# Tiny_Tetris_v1_1.net
KiCad netlist of a schematic drawn in EAGLE
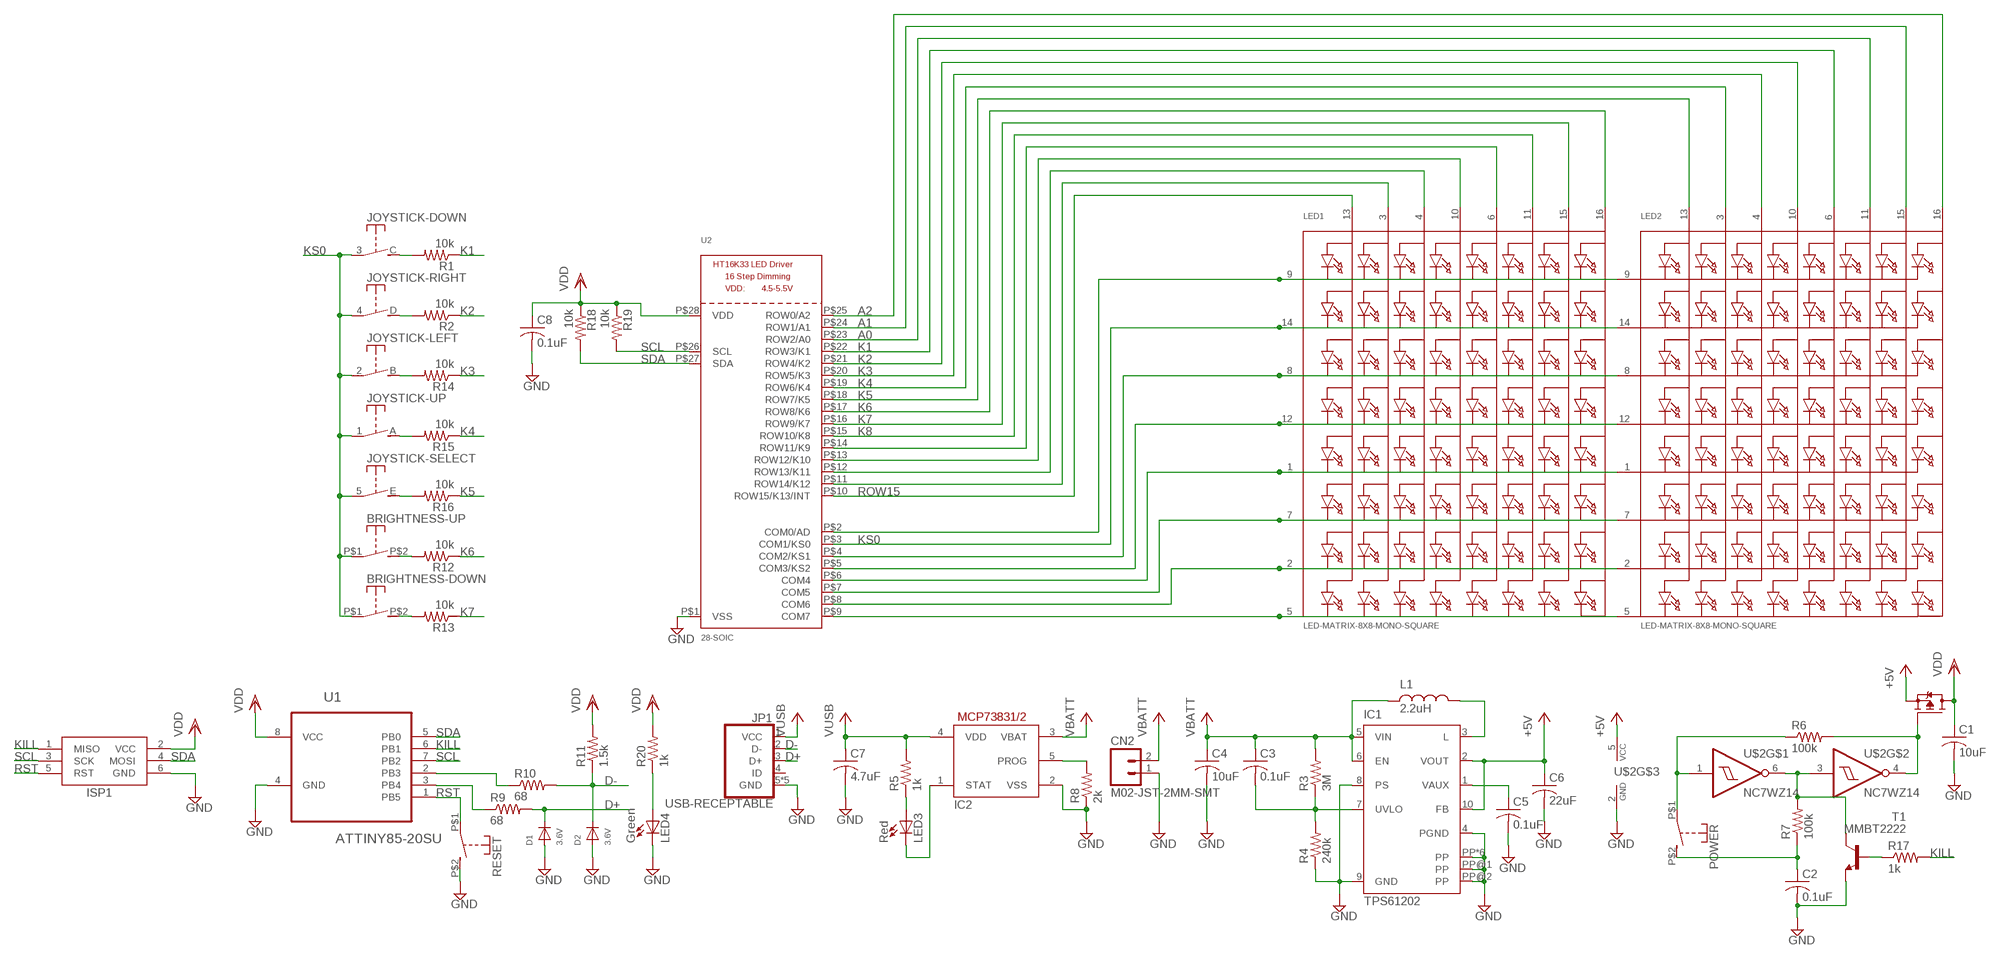
[diagram p0: schematic, sheet 1]

(export (version "E")
  (design (tool "Eeschema 10.0.6"))
  (components
    (comp (ref "BRIGHTNESS-DOWN")
      (value "SWITCH-TACTSKRELGE010")
      (footprint "eagle-import:TACT-ALPS-SKRELGE010")
      (libsource (lib "eagle-import") (part "SWITCH-TACTSKRELGE010"))
    )
    (comp (ref "BRIGHTNESS-UP")
      (value "SWITCH-TACTSKRELGE010")
      (footprint "eagle-import:TACT-ALPS-SKRELGE010")
      (libsource (lib "eagle-import") (part "SWITCH-TACTSKRELGE010"))
    )
    (comp (ref "C1")
      (value "10uF")
      (footprint "eagle-import:C0603K")
      (libsource (lib "eagle-import") (part "C-USC0603K"))
    )
    (comp (ref "C2")
      (value "0.1uF")
      (footprint "eagle-import:C0603K")
      (libsource (lib "eagle-import") (part "C-USC0603K"))
    )
    (comp (ref "C3")
      (value "0.1uF")
      (footprint "eagle-import:C0603K")
      (libsource (lib "eagle-import") (part "C-USC0603K"))
    )
    (comp (ref "C4")
      (value "10uF")
      (footprint "eagle-import:C0603K")
      (libsource (lib "eagle-import") (part "C-USC0603K"))
    )
    (comp (ref "C5")
      (value "0.1uF")
      (footprint "eagle-import:C0603K")
      (libsource (lib "eagle-import") (part "C-USC0603K"))
    )
    (comp (ref "C6")
      (value "22uF")
      (footprint "eagle-import:C0603K")
      (libsource (lib "eagle-import") (part "C-USC0603K"))
    )
    (comp (ref "C7")
      (value "4.7uF")
      (footprint "eagle-import:C0603K")
      (libsource (lib "eagle-import") (part "C-USC0603K"))
    )
    (comp (ref "C8")
      (value "0.1uF")
      (footprint "eagle-import:C0603K")
      (libsource (lib "eagle-import") (part "C-USC0603K"))
    )
    (comp (ref "CN2")
      (value "M02-JST-2MM-SMT")
      (footprint "eagle-import:1X02_NO_SILK")
      (libsource (lib "eagle-import") (part "M021X02_NO_SILK"))
    )
    (comp (ref "D1")
      (value "3.6V")
      (footprint "eagle-import:SOD-323")
      (libsource (lib "eagle-import") (part "DIODESOD-323"))
    )
    (comp (ref "D2")
      (value "3.6V")
      (footprint "eagle-import:SOD-323")
      (libsource (lib "eagle-import") (part "DIODESOD-323"))
    )
    (comp (ref "IC1")
      (value "TPS61202")
      (footprint "eagle-import:S-PDSO-N10")
      (fields (field (name "MPN") "TPS61202DRCR"))
      (libsource (lib "eagle-import") (part "TPS61202"))
    )
    (comp (ref "IC2")
      (value "MCP73831/OT")
      (footprint "eagle-import:SOT23-5L")
      (libsource (lib "eagle-import") (part "MCP73831/OT"))
    )
    (comp (ref "ISP1")
      (value "AVRISP-6")
      (footprint "eagle-import:AVRISP")
      (libsource (lib "eagle-import") (part "AVRISP-6"))
    )
    (comp (ref "JOYSTICK-")
      (value "SWITCH-NAVIGATION")
      (footprint "eagle-import:JOYSTICK-NOKIA-3230")
      (libsource (lib "eagle-import") (part "SWITCH-NAVIGATION"))
    )
    (comp (ref "JP1")
      (value "USB-RECEPTABLE")
      (footprint "eagle-import:FCI-10103594-0001LF")
      (libsource (lib "eagle-import") (part "USB-RECEPTABLE"))
    )
    (comp (ref "L1")
      (value "2.2uH")
      (footprint "eagle-import:LPS3015")
      (libsource (lib "eagle-import") (part "LPS3015"))
    )
    (comp (ref "LED1")
      (value "LED-MATRIX-8X8-MONO-SQUARE")
      (footprint "eagle-import:LED-MATRIX-8X8-MONO-SQUARE")
      (libsource (lib "eagle-import") (part "LED-MATRIX-8X8-MONO-SQUARE"))
    )
    (comp (ref "LED2")
      (value "LED-MATRIX-8X8-MONO-SQUARE")
      (footprint "eagle-import:LED-MATRIX-8X8-MONO-SQUARE")
      (libsource (lib "eagle-import") (part "LED-MATRIX-8X8-MONO-SQUARE"))
    )
    (comp (ref "LED3")
      (value "Red")
      (footprint "eagle-import:LED-0603-SIDEVIEW")
      (libsource (lib "eagle-import") (part "LED"))
    )
    (comp (ref "LED4")
      (value "Green")
      (footprint "eagle-import:LED-0603-SIDEVIEW")
      (libsource (lib "eagle-import") (part "LED"))
    )
    (comp (ref "POWER")
      (value "SWITCH-TACTSKRELGE010")
      (footprint "eagle-import:TACT-ALPS-SKRELGE010")
      (libsource (lib "eagle-import") (part "SWITCH-TACTSKRELGE010"))
    )
    (comp (ref "R1")
      (value "10k")
      (footprint "eagle-import:R0603")
      (libsource (lib "eagle-import") (part "R-US_R0603"))
    )
    (comp (ref "R2")
      (value "10k")
      (footprint "eagle-import:R0603")
      (libsource (lib "eagle-import") (part "R-US_R0603"))
    )
    (comp (ref "R3")
      (value "3M")
      (footprint "eagle-import:R0603")
      (libsource (lib "eagle-import") (part "R-US_R0603"))
    )
    (comp (ref "R4")
      (value "240k")
      (footprint "eagle-import:R0603")
      (libsource (lib "eagle-import") (part "R-US_R0603"))
    )
    (comp (ref "R5")
      (value "1k")
      (footprint "eagle-import:R0603")
      (libsource (lib "eagle-import") (part "R-US_R0603"))
    )
    (comp (ref "R6")
      (value "100k")
      (footprint "eagle-import:R0603")
      (libsource (lib "eagle-import") (part "R-US_R0603"))
    )
    (comp (ref "R7")
      (value "100k")
      (footprint "eagle-import:R0603")
      (libsource (lib "eagle-import") (part "R-US_R0603"))
    )
    (comp (ref "R8")
      (value "2k")
      (footprint "eagle-import:R0603")
      (libsource (lib "eagle-import") (part "R-US_R0603"))
    )
    (comp (ref "R9")
      (value "68")
      (footprint "eagle-import:R0603")
      (libsource (lib "eagle-import") (part "R-US_R0603"))
    )
    (comp (ref "R10")
      (value "68")
      (footprint "eagle-import:R0603")
      (libsource (lib "eagle-import") (part "R-US_R0603"))
    )
    (comp (ref "R11")
      (value "1.5k")
      (footprint "eagle-import:R0603")
      (libsource (lib "eagle-import") (part "R-US_R0603"))
    )
    (comp (ref "R12")
      (value "10k")
      (footprint "eagle-import:R0603")
      (libsource (lib "eagle-import") (part "R-US_R0603"))
    )
    (comp (ref "R13")
      (value "10k")
      (footprint "eagle-import:R0603")
      (libsource (lib "eagle-import") (part "R-US_R0603"))
    )
    (comp (ref "R14")
      (value "10k")
      (footprint "eagle-import:R0603")
      (libsource (lib "eagle-import") (part "R-US_R0603"))
    )
    (comp (ref "R15")
      (value "10k")
      (footprint "eagle-import:R0603")
      (libsource (lib "eagle-import") (part "R-US_R0603"))
    )
    (comp (ref "R16")
      (value "10k")
      (footprint "eagle-import:R0603")
      (libsource (lib "eagle-import") (part "R-US_R0603"))
    )
    (comp (ref "R17")
      (value "1k")
      (footprint "eagle-import:R0603")
      (libsource (lib "eagle-import") (part "R-US_R0603"))
    )
    (comp (ref "R18")
      (value "10k")
      (footprint "eagle-import:R0603")
      (libsource (lib "eagle-import") (part "R-US_R0603"))
    )
    (comp (ref "R19")
      (value "10k")
      (footprint "eagle-import:R0603")
      (libsource (lib "eagle-import") (part "R-US_R0603"))
    )
    (comp (ref "R20")
      (value "1k")
      (footprint "eagle-import:R0603")
      (libsource (lib "eagle-import") (part "R-US_R0603"))
    )
    (comp (ref "RESET")
      (value "SWITCH-TACTSKRELGE010")
      (footprint "eagle-import:TACT-ALPS-SKRELGE010")
      (libsource (lib "eagle-import") (part "SWITCH-TACTSKRELGE010"))
    )
    (comp (ref "T1")
      (value "MMBT2222")
      (footprint "eagle-import:SOT23-BEC")
      (libsource (lib "eagle-import") (part "-NPN-SOT23-BECMMBT2222ALT1"))
    )
    (comp (ref "U$1")
      (value "IRLML6402")
      (footprint "eagle-import:SOT23")
      (libsource (lib "eagle-import") (part "IRLML6402"))
    )
    (comp (ref "U$2")
      (value "NC7WZ14")
      (footprint "eagle-import:SC-70-6")
      (libsource (lib "eagle-import") (part "NC7WZ14"))
    )
    (comp (ref "U1")
      (value "ATTINY85-20SU")
      (footprint "eagle-import:SOIC127P798X216-8N")
      (libsource (lib "eagle-import") (part "ATTINY85-20SU"))
    )
    (comp (ref "U2")
      (value "28-SOIC")
      (footprint "eagle-import:SOP28_300MIL")
      (libsource (lib "eagle-import") (part "HT16K33_SOP28"))
    )
  )
  (nets
    (net (code "1") (name "+5V") (class "Default")
      (node (ref "C6") (pin "1") (pinfunction "1_1") (pintype "passive"))
      (node (ref "IC1") (pin "10") (pinfunction "FB_10") (pintype "input"))
      (node (ref "IC1") (pin "2") (pinfunction "VOUT_2") (pintype "passive"))
      (node (ref "U$1") (pin "2") (pinfunction "S_2") (pintype "passive"))
      (node (ref "U$2") (pin "5") (pinfunction "VCC_5") (pintype "power_in"))
    )
    (net (code "2") (name "/A0") (class "Default")
      (node (ref "LED2") (pin "11") (pinfunction "A6_11") (pintype "bidirectional"))
      (node (ref "U2") (pin "P$23") (pinfunction "ROW2/A0_P$23") (pintype "bidirectional"))
    )
    (net (code "3") (name "/A1") (class "Default")
      (node (ref "LED2") (pin "15") (pinfunction "A7_15") (pintype "bidirectional"))
      (node (ref "U2") (pin "P$24") (pinfunction "ROW1/A1_P$24") (pintype "bidirectional"))
    )
    (net (code "4") (name "/A2") (class "Default")
      (node (ref "LED2") (pin "16") (pinfunction "A8_16") (pintype "bidirectional"))
      (node (ref "U2") (pin "P$25") (pinfunction "ROW0/A2_P$25") (pintype "bidirectional"))
    )
    (net (code "5") (name "/D+") (class "Default")
      (node (ref "D1") (pin "C") (pinfunction "C_C") (pintype "passive"))
      (node (ref "JP1") (pin "3") (pinfunction "D+_3") (pintype "bidirectional"))
      (node (ref "R9") (pin "2") (pinfunction "2_2") (pintype "passive"))
    )
    (net (code "6") (name "/D-") (class "Default")
      (node (ref "D2") (pin "C") (pinfunction "C_C") (pintype "passive"))
      (node (ref "JP1") (pin "2") (pinfunction "D-_2") (pintype "bidirectional"))
      (node (ref "R10") (pin "2") (pinfunction "2_2") (pintype "passive"))
      (node (ref "R11") (pin "1") (pinfunction "1_1") (pintype "passive"))
    )
    (net (code "7") (name "/K1") (class "Default")
      (node (ref "LED2") (pin "6") (pinfunction "A5_6") (pintype "bidirectional"))
      (node (ref "R1") (pin "1") (pinfunction "1_1") (pintype "passive"))
      (node (ref "U2") (pin "P$22") (pinfunction "ROW3/K1_P$22") (pintype "bidirectional"))
    )
    (net (code "8") (name "/K2") (class "Default")
      (node (ref "LED2") (pin "10") (pinfunction "A4_10") (pintype "bidirectional"))
      (node (ref "R2") (pin "1") (pinfunction "1_1") (pintype "passive"))
      (node (ref "U2") (pin "P$21") (pinfunction "ROW4/K2_P$21") (pintype "bidirectional"))
    )
    (net (code "9") (name "/K3") (class "Default")
      (node (ref "LED2") (pin "4") (pinfunction "A3_4") (pintype "bidirectional"))
      (node (ref "R14") (pin "1") (pinfunction "1_1") (pintype "passive"))
      (node (ref "U2") (pin "P$20") (pinfunction "ROW5/K3_P$20") (pintype "bidirectional"))
    )
    (net (code "10") (name "/K4") (class "Default")
      (node (ref "LED2") (pin "3") (pinfunction "A2_3") (pintype "bidirectional"))
      (node (ref "R15") (pin "1") (pinfunction "1_1") (pintype "passive"))
      (node (ref "U2") (pin "P$19") (pinfunction "ROW6/K4_P$19") (pintype "bidirectional"))
    )
    (net (code "11") (name "/K5") (class "Default")
      (node (ref "LED2") (pin "13") (pinfunction "A1_13") (pintype "bidirectional"))
      (node (ref "R16") (pin "1") (pinfunction "1_1") (pintype "passive"))
      (node (ref "U2") (pin "P$18") (pinfunction "ROW7/K5_P$18") (pintype "bidirectional"))
    )
    (net (code "12") (name "/K6") (class "Default")
      (node (ref "LED1") (pin "16") (pinfunction "A8_16") (pintype "bidirectional"))
      (node (ref "R12") (pin "1") (pinfunction "1_1") (pintype "passive"))
      (node (ref "U2") (pin "P$17") (pinfunction "ROW8/K6_P$17") (pintype "bidirectional"))
    )
    (net (code "13") (name "/K7") (class "Default")
      (node (ref "LED1") (pin "15") (pinfunction "A7_15") (pintype "bidirectional"))
      (node (ref "R13") (pin "1") (pinfunction "1_1") (pintype "passive"))
      (node (ref "U2") (pin "P$16") (pinfunction "ROW9/K7_P$16") (pintype "bidirectional"))
    )
    (net (code "14") (name "/K8") (class "Default")
      (node (ref "LED1") (pin "11") (pinfunction "A6_11") (pintype "bidirectional"))
      (node (ref "U2") (pin "P$15") (pinfunction "ROW10/K8_P$15") (pintype "bidirectional"))
    )
    (net (code "15") (name "/KILL") (class "Default")
      (node (ref "ISP1") (pin "1") (pinfunction "MISO_1") (pintype "input"))
      (node (ref "R17") (pin "2") (pinfunction "2_2") (pintype "passive"))
      (node (ref "U1") (pin "6") (pinfunction "PB1_6") (pintype "bidirectional"))
    )
    (net (code "16") (name "/KS0") (class "Default")
      (node (ref "BRIGHTNESS-DOWN") (pin "P$1") (pinfunction "P_P$1") (pintype "passive"))
      (node (ref "BRIGHTNESS-UP") (pin "P$1") (pinfunction "P_P$1") (pintype "passive"))
      (node (ref "JOYSTICK-") (pin "1") (pinfunction "P_1") (pintype "passive"))
      (node (ref "JOYSTICK-") (pin "2") (pinfunction "P_2") (pintype "passive"))
      (node (ref "JOYSTICK-") (pin "3") (pinfunction "P_3") (pintype "passive"))
      (node (ref "JOYSTICK-") (pin "4") (pinfunction "P_4") (pintype "passive"))
      (node (ref "JOYSTICK-") (pin "5") (pinfunction "P_5") (pintype "passive"))
      (node (ref "LED1") (pin "14") (pinfunction "K2_14") (pintype "bidirectional"))
      (node (ref "LED2") (pin "14") (pinfunction "K2_14") (pintype "bidirectional"))
      (node (ref "U2") (pin "P$3") (pinfunction "COM1/KS0_P$3") (pintype "bidirectional"))
    )
    (net (code "17") (name "/ROW15") (class "Default")
      (node (ref "LED1") (pin "13") (pinfunction "A1_13") (pintype "bidirectional"))
      (node (ref "U2") (pin "P$10") (pinfunction "ROW15/K13/INT_P$10") (pintype "bidirectional"))
    )
    (net (code "18") (name "/RST") (class "Default")
      (node (ref "ISP1") (pin "5") (pinfunction "RST_5") (pintype "output"))
      (node (ref "RESET") (pin "P$1") (pinfunction "P_P$1") (pintype "passive"))
      (node (ref "U1") (pin "1") (pinfunction "PB5_1") (pintype "bidirectional"))
    )
    (net (code "19") (name "/SCL") (class "Default")
      (node (ref "ISP1") (pin "3") (pinfunction "SCK_3") (pintype "output"))
      (node (ref "R19") (pin "2") (pinfunction "2_2") (pintype "passive"))
      (node (ref "U1") (pin "7") (pinfunction "PB2_7") (pintype "bidirectional"))
      (node (ref "U2") (pin "P$26") (pinfunction "SCL_P$26") (pintype "bidirectional"))
    )
    (net (code "20") (name "/SDA") (class "Default")
      (node (ref "ISP1") (pin "4") (pinfunction "MOSI_4") (pintype "output"))
      (node (ref "R18") (pin "2") (pinfunction "2_2") (pintype "passive"))
      (node (ref "U1") (pin "5") (pinfunction "PB0_5") (pintype "bidirectional"))
      (node (ref "U2") (pin "P$27") (pinfunction "SDA_P$27") (pintype "bidirectional"))
    )
    (net (code "21") (name "GND") (class "Default")
      (node (ref "C1") (pin "2") (pinfunction "2_2") (pintype "passive"))
      (node (ref "C2") (pin "2") (pinfunction "2_2") (pintype "passive"))
      (node (ref "C4") (pin "2") (pinfunction "2_2") (pintype "passive"))
      (node (ref "C5") (pin "2") (pinfunction "2_2") (pintype "passive"))
      (node (ref "C6") (pin "2") (pinfunction "2_2") (pintype "passive"))
      (node (ref "C7") (pin "2") (pinfunction "2_2") (pintype "passive"))
      (node (ref "C8") (pin "2") (pinfunction "2_2") (pintype "passive"))
      (node (ref "CN2") (pin "1") (pinfunction "1_1") (pintype "passive"))
      (node (ref "D1") (pin "A") (pinfunction "A_A") (pintype "passive"))
      (node (ref "D2") (pin "A") (pinfunction "A_A") (pintype "passive"))
      (node (ref "IC1") (pin "4") (pinfunction "PGND_4") (pintype "power_in"))
      (node (ref "IC1") (pin "8") (pinfunction "PS_8") (pintype "input"))
      (node (ref "IC1") (pin "9") (pinfunction "GND_9") (pintype "power_in"))
      (node (ref "IC1") (pin "PP") (pinfunction "PP_PP") (pintype "power_in"))
      (node (ref "IC1") (pin "PP@1") (pinfunction "PP_PP@1") (pintype "power_in"))
      (node (ref "IC1") (pin "PP@2") (pinfunction "PP_PP@2") (pintype "power_in"))
      (node (ref "IC1") (pin "PP@3") (pinfunction "PP_PP@3") (pintype "power_in"))
      (node (ref "IC1") (pin "PP@4") (pinfunction "PP_PP@4") (pintype "power_in"))
      (node (ref "IC1") (pin "PP@5") (pinfunction "PP_PP@5") (pintype "power_in"))
      (node (ref "IC1") (pin "PP@6") (pinfunction "PP_PP@6") (pintype "power_in"))
      (node (ref "IC1") (pin "PP@7") (pinfunction "PP_PP@7") (pintype "power_in"))
      (node (ref "IC2") (pin "2") (pinfunction "VSS_2") (pintype "power_in"))
      (node (ref "ISP1") (pin "6") (pinfunction "GND_6") (pintype "power_in"))
      (node (ref "JP1") (pin "5") (pinfunction "GND_5") (pintype "bidirectional"))
      (node (ref "JP1") (pin "P$1") (pinfunction "GND_P$1") (pintype "bidirectional"))
      (node (ref "JP1") (pin "P$2") (pinfunction "GND_P$2") (pintype "bidirectional"))
      (node (ref "JP1") (pin "P$3") (pinfunction "GND_P$3") (pintype "bidirectional"))
      (node (ref "JP1") (pin "P$4") (pinfunction "GND_P$4") (pintype "bidirectional"))
      (node (ref "LED4") (pin "P$2") (pinfunction "C_P$2") (pintype "passive"))
      (node (ref "R4") (pin "1") (pinfunction "1_1") (pintype "passive"))
      (node (ref "R8") (pin "1") (pinfunction "1_1") (pintype "passive"))
      (node (ref "RESET") (pin "P$2") (pinfunction "S_P$2") (pintype "passive"))
      (node (ref "T1") (pin "E") (pinfunction "E_E") (pintype "passive"))
      (node (ref "U$2") (pin "2") (pinfunction "GND_2") (pintype "power_in"))
      (node (ref "U1") (pin "4") (pinfunction "GND_4") (pintype "passive"))
      (node (ref "U2") (pin "P$1") (pinfunction "VSS_P$1") (pintype "bidirectional"))
    )
    (net (code "22") (name "Net-(BRIGHTNESS-DOWN-S)") (class "Default")
      (node (ref "BRIGHTNESS-DOWN") (pin "P$2") (pinfunction "S_P$2") (pintype "passive"))
      (node (ref "R13") (pin "2") (pinfunction "2_2") (pintype "passive"))
    )
    (net (code "23") (name "Net-(BRIGHTNESS-UP-S)") (class "Default")
      (node (ref "BRIGHTNESS-UP") (pin "P$2") (pinfunction "S_P$2") (pintype "passive"))
      (node (ref "R12") (pin "2") (pinfunction "2_2") (pintype "passive"))
    )
    (net (code "24") (name "Net-(IC1-L)") (class "Default")
      (node (ref "IC1") (pin "3") (pinfunction "L_3") (pintype "input"))
      (node (ref "L1") (pin "P$2") (pinfunction "P$2_P$2") (pintype "bidirectional"))
    )
    (net (code "25") (name "Net-(IC1-UVLO)") (class "Default")
      (node (ref "C3") (pin "2") (pinfunction "2_2") (pintype "passive"))
      (node (ref "IC1") (pin "7") (pinfunction "UVLO_7") (pintype "input"))
      (node (ref "R3") (pin "1") (pinfunction "1_1") (pintype "passive"))
      (node (ref "R4") (pin "2") (pinfunction "2_2") (pintype "passive"))
    )
    (net (code "26") (name "Net-(IC1-VAUX)") (class "Default")
      (node (ref "C5") (pin "1") (pinfunction "1_1") (pintype "passive"))
      (node (ref "IC1") (pin "1") (pinfunction "VAUX_1") (pintype "bidirectional"))
    )
    (net (code "27") (name "Net-(IC2-PROG)") (class "Default")
      (node (ref "IC2") (pin "5") (pinfunction "PROG_5") (pintype "input"))
      (node (ref "R8") (pin "2") (pinfunction "2_2") (pintype "passive"))
    )
    (net (code "28") (name "Net-(IC2-STAT)") (class "Default")
      (node (ref "IC2") (pin "1") (pinfunction "STAT_1") (pintype "output"))
      (node (ref "LED3") (pin "P$2") (pinfunction "C_P$2") (pintype "passive"))
    )
    (net (code "29") (name "Net-(JOYSTICK-A-S)") (class "Default")
      (node (ref "JOYSTICK-") (pin "C") (pinfunction "S_C") (pintype "passive"))
      (node (ref "R1") (pin "2") (pinfunction "2_2") (pintype "passive"))
    )
    (net (code "30") (name "Net-(JOYSTICK-B-S)") (class "Default")
      (node (ref "JOYSTICK-") (pin "B") (pinfunction "S_B") (pintype "passive"))
      (node (ref "R14") (pin "2") (pinfunction "2_2") (pintype "passive"))
    )
    (net (code "31") (name "Net-(JOYSTICK-C-S)") (class "Default")
      (node (ref "JOYSTICK-") (pin "D") (pinfunction "S_D") (pintype "passive"))
      (node (ref "R2") (pin "2") (pinfunction "2_2") (pintype "passive"))
    )
    (net (code "32") (name "Net-(JOYSTICK-D-S)") (class "Default")
      (node (ref "JOYSTICK-") (pin "E") (pinfunction "S_E") (pintype "passive"))
      (node (ref "R16") (pin "2") (pinfunction "2_2") (pintype "passive"))
    )
    (net (code "33") (name "Net-(JOYSTICK-E-S)") (class "Default")
      (node (ref "JOYSTICK-") (pin "A") (pinfunction "S_A") (pintype "passive"))
      (node (ref "R15") (pin "2") (pinfunction "2_2") (pintype "passive"))
    )
    (net (code "34") (name "Net-(LED1-A2)") (class "Default")
      (node (ref "LED1") (pin "3") (pinfunction "A2_3") (pintype "bidirectional"))
      (node (ref "U2") (pin "P$11") (pinfunction "ROW14/K12_P$11") (pintype "bidirectional"))
    )
    (net (code "35") (name "Net-(LED1-A3)") (class "Default")
      (node (ref "LED1") (pin "4") (pinfunction "A3_4") (pintype "bidirectional"))
      (node (ref "U2") (pin "P$12") (pinfunction "ROW13/K11_P$12") (pintype "bidirectional"))
    )
    (net (code "36") (name "Net-(LED1-A4)") (class "Default")
      (node (ref "LED1") (pin "10") (pinfunction "A4_10") (pintype "bidirectional"))
      (node (ref "U2") (pin "P$13") (pinfunction "ROW12/K10_P$13") (pintype "bidirectional"))
    )
    (net (code "37") (name "Net-(LED1-A5)") (class "Default")
      (node (ref "LED1") (pin "6") (pinfunction "A5_6") (pintype "bidirectional"))
      (node (ref "U2") (pin "P$14") (pinfunction "ROW11/K9_P$14") (pintype "bidirectional"))
    )
    (net (code "38") (name "Net-(LED1-K1)") (class "Default")
      (node (ref "LED1") (pin "9") (pinfunction "K1_9") (pintype "bidirectional"))
      (node (ref "LED2") (pin "9") (pinfunction "K1_9") (pintype "bidirectional"))
      (node (ref "U2") (pin "P$2") (pinfunction "COM0/AD_P$2") (pintype "bidirectional"))
    )
    (net (code "39") (name "Net-(LED1-K3)") (class "Default")
      (node (ref "LED1") (pin "8") (pinfunction "K3_8") (pintype "bidirectional"))
      (node (ref "LED2") (pin "8") (pinfunction "K3_8") (pintype "bidirectional"))
      (node (ref "U2") (pin "P$4") (pinfunction "COM2/KS1_P$4") (pintype "bidirectional"))
    )
    (net (code "40") (name "Net-(LED1-K4)") (class "Default")
      (node (ref "LED1") (pin "12") (pinfunction "K4_12") (pintype "bidirectional"))
      (node (ref "LED2") (pin "12") (pinfunction "K4_12") (pintype "bidirectional"))
      (node (ref "U2") (pin "P$5") (pinfunction "COM3/KS2_P$5") (pintype "bidirectional"))
    )
    (net (code "41") (name "Net-(LED1-K5)") (class "Default")
      (node (ref "LED1") (pin "1") (pinfunction "K5_1") (pintype "bidirectional"))
      (node (ref "LED2") (pin "1") (pinfunction "K5_1") (pintype "bidirectional"))
      (node (ref "U2") (pin "P$6") (pinfunction "COM4_P$6") (pintype "bidirectional"))
    )
    (net (code "42") (name "Net-(LED1-K6)") (class "Default")
      (node (ref "LED1") (pin "7") (pinfunction "K6_7") (pintype "bidirectional"))
      (node (ref "LED2") (pin "7") (pinfunction "K6_7") (pintype "bidirectional"))
      (node (ref "U2") (pin "P$7") (pinfunction "COM5_P$7") (pintype "bidirectional"))
    )
    (net (code "43") (name "Net-(LED1-K7)") (class "Default")
      (node (ref "LED1") (pin "2") (pinfunction "K7_2") (pintype "bidirectional"))
      (node (ref "LED2") (pin "2") (pinfunction "K7_2") (pintype "bidirectional"))
      (node (ref "U2") (pin "P$8") (pinfunction "COM6_P$8") (pintype "bidirectional"))
    )
    (net (code "44") (name "Net-(LED1-K8)") (class "Default")
      (node (ref "LED1") (pin "5") (pinfunction "K8_5") (pintype "bidirectional"))
      (node (ref "LED2") (pin "5") (pinfunction "K8_5") (pintype "bidirectional"))
      (node (ref "U2") (pin "P$9") (pinfunction "COM7_P$9") (pintype "bidirectional"))
    )
    (net (code "45") (name "Net-(LED3-A)") (class "Default")
      (node (ref "LED3") (pin "P$1") (pinfunction "A_P$1") (pintype "passive"))
      (node (ref "R5") (pin "1") (pinfunction "1_1") (pintype "passive"))
    )
    (net (code "46") (name "Net-(LED4-A)") (class "Default")
      (node (ref "LED4") (pin "P$1") (pinfunction "A_P$1") (pintype "passive"))
      (node (ref "R20") (pin "1") (pinfunction "1_1") (pintype "passive"))
    )
    (net (code "47") (name "Net-(POWER-P)") (class "Default")
      (node (ref "POWER") (pin "P$1") (pinfunction "P_P$1") (pintype "passive"))
      (node (ref "R6") (pin "1") (pinfunction "1_1") (pintype "passive"))
      (node (ref "U$2") (pin "1") (pinfunction "I_1") (pintype "input"))
    )
    (net (code "48") (name "Net-(POWER-S)") (class "Default")
      (node (ref "C2") (pin "1") (pinfunction "1_1") (pintype "passive"))
      (node (ref "POWER") (pin "P$2") (pinfunction "S_P$2") (pintype "passive"))
      (node (ref "R7") (pin "1") (pinfunction "1_1") (pintype "passive"))
    )
    (net (code "49") (name "Net-(R17-Pad1)") (class "Default")
      (node (ref "R17") (pin "1") (pinfunction "1_1") (pintype "passive"))
      (node (ref "T1") (pin "B") (pinfunction "B_B") (pintype "passive"))
    )
    (net (code "50") (name "Net-(U$1-G)") (class "Default")
      (node (ref "R6") (pin "2") (pinfunction "2_2") (pintype "passive"))
      (node (ref "U$1") (pin "1") (pinfunction "G_1") (pintype "passive"))
      (node (ref "U$2") (pin "4") (pinfunction "O_4") (pintype "output"))
    )
    (net (code "51") (name "Net-(U$2A-O)") (class "Default")
      (node (ref "R7") (pin "2") (pinfunction "2_2") (pintype "passive"))
      (node (ref "T1") (pin "C") (pinfunction "C_C") (pintype "passive"))
      (node (ref "U$2") (pin "3") (pinfunction "I_3") (pintype "input"))
      (node (ref "U$2") (pin "6") (pinfunction "O_6") (pintype "output"))
    )
    (net (code "52") (name "Net-(U1-PB3)") (class "Default")
      (node (ref "R10") (pin "1") (pinfunction "1_1") (pintype "passive"))
      (node (ref "U1") (pin "2") (pinfunction "PB3_2") (pintype "bidirectional"))
    )
    (net (code "53") (name "Net-(U1-PB4)") (class "Default")
      (node (ref "R9") (pin "1") (pinfunction "1_1") (pintype "passive"))
      (node (ref "U1") (pin "3") (pinfunction "PB4_3") (pintype "bidirectional"))
    )
    (net (code "54") (name "VBATT") (class "Default")
      (node (ref "C3") (pin "1") (pinfunction "1_1") (pintype "passive"))
      (node (ref "C4") (pin "1") (pinfunction "1_1") (pintype "passive"))
      (node (ref "CN2") (pin "2") (pinfunction "2_2") (pintype "passive"))
      (node (ref "IC1") (pin "5") (pinfunction "VIN_5") (pintype "input"))
      (node (ref "IC1") (pin "6") (pinfunction "EN_6") (pintype "input"))
      (node (ref "IC2") (pin "3") (pinfunction "VBAT_3") (pintype "bidirectional"))
      (node (ref "L1") (pin "P$1") (pinfunction "P$1_P$1") (pintype "bidirectional"))
      (node (ref "R3") (pin "2") (pinfunction "2_2") (pintype "passive"))
    )
    (net (code "55") (name "VDD") (class "Default")
      (node (ref "C1") (pin "1") (pinfunction "1_1") (pintype "passive"))
      (node (ref "C8") (pin "1") (pinfunction "1_1") (pintype "passive"))
      (node (ref "ISP1") (pin "2") (pinfunction "VCC_2") (pintype "power_in"))
      (node (ref "R11") (pin "2") (pinfunction "2_2") (pintype "passive"))
      (node (ref "R18") (pin "1") (pinfunction "1_1") (pintype "passive"))
      (node (ref "R19") (pin "1") (pinfunction "1_1") (pintype "passive"))
      (node (ref "R20") (pin "2") (pinfunction "2_2") (pintype "passive"))
      (node (ref "U$1") (pin "3") (pinfunction "D_3") (pintype "passive"))
      (node (ref "U1") (pin "8") (pinfunction "VCC_8") (pintype "power_in"))
      (node (ref "U2") (pin "P$28") (pinfunction "VDD_P$28") (pintype "bidirectional"))
    )
    (net (code "56") (name "VUSB") (class "Default")
      (node (ref "C7") (pin "1") (pinfunction "1_1") (pintype "passive"))
      (node (ref "IC2") (pin "4") (pinfunction "VDD_4") (pintype "power_in"))
      (node (ref "JP1") (pin "1") (pinfunction "VCC_1") (pintype "bidirectional"))
      (node (ref "R5") (pin "2") (pinfunction "2_2") (pintype "passive"))
    )
    (net (code "57") (name "unconnected-(JP1-ID-Pad4)") (class "Default")
      (node (ref "JP1") (pin "4") (pinfunction "ID_4") (pintype "bidirectional"))
    )
  )
)
